# MIPI.net
KiCad netlist of a schematic drawn in Altium Designer
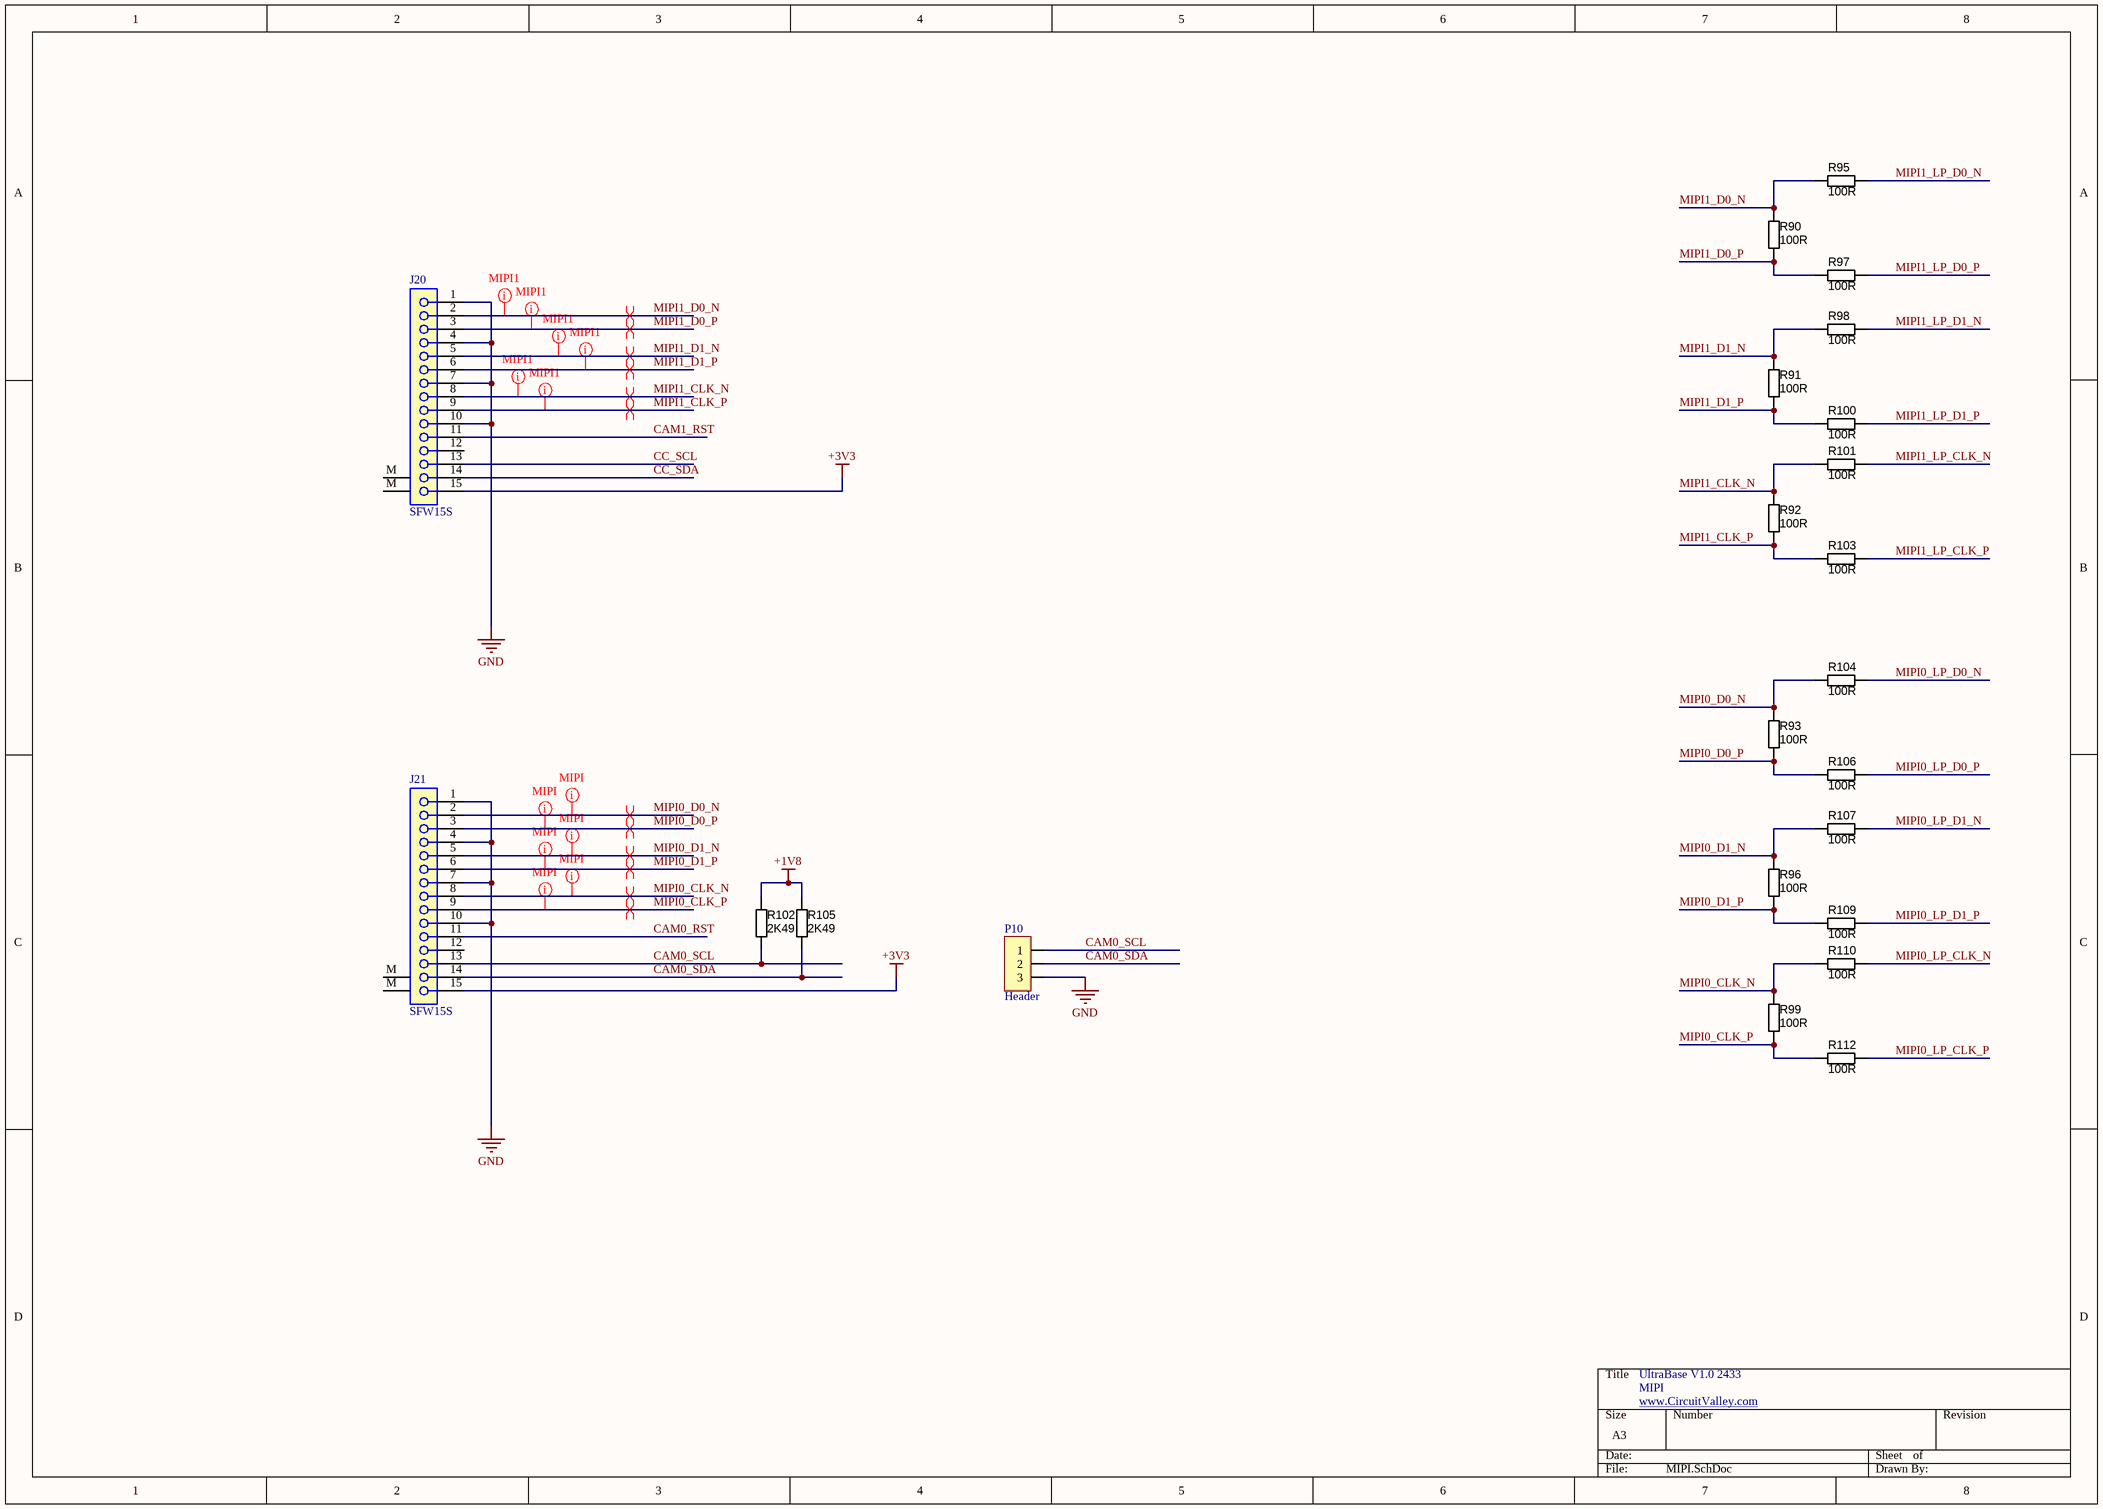
[diagram p0: MIPI.SchDoc]

(export (version "E")
  (design (tool "Eeschema 10.0.6"))
  (components
    (comp (ref "J20")
      (value "SFW15S")
      (footprint "SFW15S-2STMAE1LF")
      (description "15 pin 1mm FPC, RPI Camera")
      (libsource (lib "cvlib") (part "SFW15S"))
    )
    (comp (ref "J21")
      (value "SFW15S")
      (footprint "SFW15S-2STMAE1LF")
      (description "15 pin 1mm FPC, RPI Camera")
      (libsource (lib "cvlib") (part "SFW15S"))
    )
    (comp (ref "P10")
      (value "Header")
      (footprint "Header3x")
      (description "3 Pin Header")
      (libsource (lib "cvlib") (part "Header_3Pin"))
    )
    (comp (ref "R90")
      (value "100R")
      (footprint "RESC1005N")
      (description "Resistor SMD chip 3.3k Ohm 0.063W 5% 0402")
      (fields (field (name "TOLERANCE") "±5%") (field (name "Comment") "Thick Film"))
      (libsource (lib "PBL - Resistors") (part "RES_3K3_0402_5%"))
    )
    (comp (ref "R91")
      (value "100R")
      (footprint "RESC1005N")
      (description "Resistor SMD chip 3.3k Ohm 0.063W 5% 0402")
      (fields (field (name "TOLERANCE") "±5%") (field (name "Comment") "Thick Film"))
      (libsource (lib "PBL - Resistors") (part "RES_3K3_0402_5%"))
    )
    (comp (ref "R92")
      (value "100R")
      (footprint "RESC1005N")
      (description "Resistor SMD chip 3.3k Ohm 0.063W 5% 0402")
      (fields (field (name "TOLERANCE") "±5%") (field (name "Comment") "Thick Film"))
      (libsource (lib "PBL - Resistors") (part "RES_3K3_0402_5%"))
    )
    (comp (ref "R93")
      (value "100R")
      (footprint "RESC1005N")
      (description "Resistor SMD chip 3.3k Ohm 0.063W 5% 0402")
      (fields (field (name "TOLERANCE") "±5%") (field (name "Comment") "Thick Film"))
      (libsource (lib "PBL - Resistors") (part "RES_3K3_0402_5%"))
    )
    (comp (ref "R95")
      (value "100R")
      (footprint "RESC1608N")
      (description "Resistor, SMD chip")
      (fields (field (name "TOLERANCE") "±5%") (field (name "Comment") "RES_NL_0603"))
      (libsource (lib "PBL - Resistors") (part "RES_NL_0603"))
    )
    (comp (ref "R96")
      (value "100R")
      (footprint "RESC1005N")
      (description "Resistor SMD chip 3.3k Ohm 0.063W 5% 0402")
      (fields (field (name "TOLERANCE") "±5%") (field (name "Comment") "Thick Film"))
      (libsource (lib "PBL - Resistors") (part "RES_3K3_0402_5%"))
    )
    (comp (ref "R97")
      (value "100R")
      (footprint "RESC1608N")
      (description "Resistor, SMD chip")
      (fields (field (name "TOLERANCE") "±5%") (field (name "Comment") "RES_NL_0603"))
      (libsource (lib "PBL - Resistors") (part "RES_NL_0603"))
    )
    (comp (ref "R98")
      (value "100R")
      (footprint "RESC1608N")
      (description "Resistor, SMD chip")
      (fields (field (name "TOLERANCE") "±5%") (field (name "Comment") "RES_NL_0603"))
      (libsource (lib "PBL - Resistors") (part "RES_NL_0603"))
    )
    (comp (ref "R99")
      (value "100R")
      (footprint "RESC1005N")
      (description "Resistor SMD chip 3.3k Ohm 0.063W 5% 0402")
      (fields (field (name "TOLERANCE") "±5%") (field (name "Comment") "Thick Film"))
      (libsource (lib "PBL - Resistors") (part "RES_3K3_0402_5%"))
    )
    (comp (ref "R100")
      (value "100R")
      (footprint "RESC1608N")
      (description "Resistor, SMD chip")
      (fields (field (name "TOLERANCE") "±5%") (field (name "Comment") "RES_NL_0603"))
      (libsource (lib "PBL - Resistors") (part "RES_NL_0603"))
    )
    (comp (ref "R101")
      (value "100R")
      (footprint "RESC1608N")
      (description "Resistor, SMD chip")
      (fields (field (name "TOLERANCE") "±5%") (field (name "Comment") "RES_NL_0603"))
      (libsource (lib "PBL - Resistors") (part "RES_NL_0603"))
    )
    (comp (ref "R102")
      (value "2K49")
      (footprint "RESC1608N")
      (description "Resistor, SMD chip")
      (fields (field (name "TOLERANCE") "±5%") (field (name "Comment") "RES_NL_0603"))
      (libsource (lib "") (part "RES_NL_0603_1"))
    )
    (comp (ref "R103")
      (value "100R")
      (footprint "RESC1608N")
      (description "Resistor, SMD chip")
      (fields (field (name "TOLERANCE") "±5%") (field (name "Comment") "RES_NL_0603"))
      (libsource (lib "PBL - Resistors") (part "RES_NL_0603"))
    )
    (comp (ref "R104")
      (value "100R")
      (footprint "RESC1608N")
      (description "Resistor, SMD chip")
      (fields (field (name "TOLERANCE") "±5%") (field (name "Comment") "RES_NL_0603"))
      (libsource (lib "PBL - Resistors") (part "RES_NL_0603"))
    )
    (comp (ref "R105")
      (value "2K49")
      (footprint "RESC1608N")
      (description "Resistor, SMD chip")
      (fields (field (name "TOLERANCE") "±5%") (field (name "Comment") "RES_NL_0603"))
      (libsource (lib "") (part "RES_NL_0603_1"))
    )
    (comp (ref "R106")
      (value "100R")
      (footprint "RESC1608N")
      (description "Resistor, SMD chip")
      (fields (field (name "TOLERANCE") "±5%") (field (name "Comment") "RES_NL_0603"))
      (libsource (lib "PBL - Resistors") (part "RES_NL_0603"))
    )
    (comp (ref "R107")
      (value "100R")
      (footprint "RESC1608N")
      (description "Resistor, SMD chip")
      (fields (field (name "TOLERANCE") "±5%") (field (name "Comment") "RES_NL_0603"))
      (libsource (lib "PBL - Resistors") (part "RES_NL_0603"))
    )
    (comp (ref "R109")
      (value "100R")
      (footprint "RESC1608N")
      (description "Resistor, SMD chip")
      (fields (field (name "TOLERANCE") "±5%") (field (name "Comment") "RES_NL_0603"))
      (libsource (lib "PBL - Resistors") (part "RES_NL_0603"))
    )
    (comp (ref "R110")
      (value "100R")
      (footprint "RESC1608N")
      (description "Resistor, SMD chip")
      (fields (field (name "TOLERANCE") "±5%") (field (name "Comment") "RES_NL_0603"))
      (libsource (lib "PBL - Resistors") (part "RES_NL_0603"))
    )
    (comp (ref "R112")
      (value "100R")
      (footprint "RESC1608N")
      (description "Resistor, SMD chip")
      (fields (field (name "TOLERANCE") "±5%") (field (name "Comment") "RES_NL_0603"))
      (libsource (lib "PBL - Resistors") (part "RES_NL_0603"))
    )
  )
  (nets
    (net (code "1") (name "+1V8") (class "Default")
      (node (ref "R102") (pin "2") (pinfunction "2_2") (pintype "passive"))
      (node (ref "R105") (pin "2") (pinfunction "2_2") (pintype "passive"))
    )
    (net (code "2") (name "+3V3") (class "Default")
      (node (ref "J20") (pin "15") (pinfunction "15_15") (pintype "passive"))
      (node (ref "J21") (pin "15") (pinfunction "15_15") (pintype "passive"))
    )
    (net (code "3") (name "/CAM0_RST") (class "Default")
      (node (ref "J21") (pin "11") (pinfunction "11_11") (pintype "passive"))
    )
    (net (code "4") (name "/CAM0_SCL") (class "Default")
      (node (ref "J21") (pin "13") (pinfunction "13_13") (pintype "passive"))
      (node (ref "P10") (pin "1") (pinfunction "1_1") (pintype "passive"))
      (node (ref "R102") (pin "1") (pinfunction "1_1") (pintype "passive"))
    )
    (net (code "5") (name "/CAM0_SDA") (class "Default")
      (node (ref "J21") (pin "14") (pinfunction "14_14") (pintype "passive"))
      (node (ref "P10") (pin "2") (pinfunction "2_2") (pintype "passive"))
      (node (ref "R105") (pin "1") (pinfunction "1_1") (pintype "passive"))
    )
    (net (code "6") (name "/CAM1_RST") (class "Default")
      (node (ref "J20") (pin "11") (pinfunction "11_11") (pintype "passive"))
    )
    (net (code "7") (name "/CC_SCL") (class "Default")
      (node (ref "J20") (pin "13") (pinfunction "13_13") (pintype "passive"))
    )
    (net (code "8") (name "/CC_SDA") (class "Default")
      (node (ref "J20") (pin "14") (pinfunction "14_14") (pintype "passive"))
    )
    (net (code "9") (name "/MIPI0_CLK_N") (class "Default")
      (node (ref "J21") (pin "8") (pinfunction "8_8") (pintype "passive"))
      (node (ref "R110") (pin "1") (pinfunction "1_1") (pintype "passive"))
      (node (ref "R99") (pin "1") (pinfunction "1_1") (pintype "passive"))
    )
    (net (code "10") (name "/MIPI0_CLK_P") (class "Default")
      (node (ref "J21") (pin "9") (pinfunction "9_9") (pintype "passive"))
      (node (ref "R112") (pin "1") (pinfunction "1_1") (pintype "passive"))
      (node (ref "R99") (pin "2") (pinfunction "2_2") (pintype "passive"))
    )
    (net (code "11") (name "/MIPI0_D0_N") (class "Default")
      (node (ref "J21") (pin "2") (pinfunction "2_2") (pintype "passive"))
      (node (ref "R104") (pin "1") (pinfunction "1_1") (pintype "passive"))
      (node (ref "R93") (pin "1") (pinfunction "1_1") (pintype "passive"))
    )
    (net (code "12") (name "/MIPI0_D0_P") (class "Default")
      (node (ref "J21") (pin "3") (pinfunction "3_3") (pintype "passive"))
      (node (ref "R106") (pin "1") (pinfunction "1_1") (pintype "passive"))
      (node (ref "R93") (pin "2") (pinfunction "2_2") (pintype "passive"))
    )
    (net (code "13") (name "/MIPI0_D1_N") (class "Default")
      (node (ref "J21") (pin "5") (pinfunction "5_5") (pintype "passive"))
      (node (ref "R107") (pin "1") (pinfunction "1_1") (pintype "passive"))
      (node (ref "R96") (pin "1") (pinfunction "1_1") (pintype "passive"))
    )
    (net (code "14") (name "/MIPI0_D1_P") (class "Default")
      (node (ref "J21") (pin "6") (pinfunction "6_6") (pintype "passive"))
      (node (ref "R109") (pin "1") (pinfunction "1_1") (pintype "passive"))
      (node (ref "R96") (pin "2") (pinfunction "2_2") (pintype "passive"))
    )
    (net (code "15") (name "/MIPI0_LP_CLK_N") (class "Default")
      (node (ref "R110") (pin "2") (pinfunction "2_2") (pintype "passive"))
    )
    (net (code "16") (name "/MIPI0_LP_CLK_P") (class "Default")
      (node (ref "R112") (pin "2") (pinfunction "2_2") (pintype "passive"))
    )
    (net (code "17") (name "/MIPI0_LP_D0_N") (class "Default")
      (node (ref "R104") (pin "2") (pinfunction "2_2") (pintype "passive"))
    )
    (net (code "18") (name "/MIPI0_LP_D0_P") (class "Default")
      (node (ref "R106") (pin "2") (pinfunction "2_2") (pintype "passive"))
    )
    (net (code "19") (name "/MIPI0_LP_D1_N") (class "Default")
      (node (ref "R107") (pin "2") (pinfunction "2_2") (pintype "passive"))
    )
    (net (code "20") (name "/MIPI0_LP_D1_P") (class "Default")
      (node (ref "R109") (pin "2") (pinfunction "2_2") (pintype "passive"))
    )
    (net (code "21") (name "/MIPI1_CLK_N") (class "Default")
      (node (ref "J20") (pin "8") (pinfunction "8_8") (pintype "passive"))
      (node (ref "R101") (pin "1") (pinfunction "1_1") (pintype "passive"))
      (node (ref "R92") (pin "1") (pinfunction "1_1") (pintype "passive"))
    )
    (net (code "22") (name "/MIPI1_CLK_P") (class "Default")
      (node (ref "J20") (pin "9") (pinfunction "9_9") (pintype "passive"))
      (node (ref "R103") (pin "1") (pinfunction "1_1") (pintype "passive"))
      (node (ref "R92") (pin "2") (pinfunction "2_2") (pintype "passive"))
    )
    (net (code "23") (name "/MIPI1_D0_N") (class "Default")
      (node (ref "J20") (pin "2") (pinfunction "2_2") (pintype "passive"))
      (node (ref "R90") (pin "1") (pinfunction "1_1") (pintype "passive"))
      (node (ref "R95") (pin "1") (pinfunction "1_1") (pintype "passive"))
    )
    (net (code "24") (name "/MIPI1_D0_P") (class "Default")
      (node (ref "J20") (pin "3") (pinfunction "3_3") (pintype "passive"))
      (node (ref "R90") (pin "2") (pinfunction "2_2") (pintype "passive"))
      (node (ref "R97") (pin "1") (pinfunction "1_1") (pintype "passive"))
    )
    (net (code "25") (name "/MIPI1_D1_N") (class "Default")
      (node (ref "J20") (pin "5") (pinfunction "5_5") (pintype "passive"))
      (node (ref "R91") (pin "1") (pinfunction "1_1") (pintype "passive"))
      (node (ref "R98") (pin "1") (pinfunction "1_1") (pintype "passive"))
    )
    (net (code "26") (name "/MIPI1_D1_P") (class "Default")
      (node (ref "J20") (pin "6") (pinfunction "6_6") (pintype "passive"))
      (node (ref "R100") (pin "1") (pinfunction "1_1") (pintype "passive"))
      (node (ref "R91") (pin "2") (pinfunction "2_2") (pintype "passive"))
    )
    (net (code "27") (name "/MIPI1_LP_CLK_N") (class "Default")
      (node (ref "R101") (pin "2") (pinfunction "2_2") (pintype "passive"))
    )
    (net (code "28") (name "/MIPI1_LP_CLK_P") (class "Default")
      (node (ref "R103") (pin "2") (pinfunction "2_2") (pintype "passive"))
    )
    (net (code "29") (name "/MIPI1_LP_D0_N") (class "Default")
      (node (ref "R95") (pin "2") (pinfunction "2_2") (pintype "passive"))
    )
    (net (code "30") (name "/MIPI1_LP_D0_P") (class "Default")
      (node (ref "R97") (pin "2") (pinfunction "2_2") (pintype "passive"))
    )
    (net (code "31") (name "/MIPI1_LP_D1_N") (class "Default")
      (node (ref "R98") (pin "2") (pinfunction "2_2") (pintype "passive"))
    )
    (net (code "32") (name "/MIPI1_LP_D1_P") (class "Default")
      (node (ref "R100") (pin "2") (pinfunction "2_2") (pintype "passive"))
    )
    (net (code "33") (name "GND") (class "Default")
      (node (ref "J20") (pin "1") (pinfunction "1_1") (pintype "passive"))
      (node (ref "J20") (pin "10") (pinfunction "10_10") (pintype "passive"))
      (node (ref "J20") (pin "4") (pinfunction "4_4") (pintype "passive"))
      (node (ref "J20") (pin "7") (pinfunction "7_7") (pintype "passive"))
      (node (ref "J21") (pin "1") (pinfunction "1_1") (pintype "passive"))
      (node (ref "J21") (pin "10") (pinfunction "10_10") (pintype "passive"))
      (node (ref "J21") (pin "4") (pinfunction "4_4") (pintype "passive"))
      (node (ref "J21") (pin "7") (pinfunction "7_7") (pintype "passive"))
      (node (ref "P10") (pin "3") (pinfunction "3_3") (pintype "passive"))
    )
    (net (code "34") (name "unconnected-(J20-16-PadM)") (class "Default")
      (node (ref "J20") (pin "M") (pinfunction "16_M") (pintype "passive"))
    )
    (net (code "35") (name "unconnected-(J20-17-PadM)") (class "Default")
      (node (ref "J20") (pin "M") (pinfunction "17_M") (pintype "passive"))
    )
    (net (code "36") (name "unconnected-(J20-Pad12)") (class "Default")
      (node (ref "J20") (pin "12") (pinfunction "12_12") (pintype "passive"))
    )
    (net (code "37") (name "unconnected-(J21-16-PadM)") (class "Default")
      (node (ref "J21") (pin "M") (pinfunction "16_M") (pintype "passive"))
    )
    (net (code "38") (name "unconnected-(J21-17-PadM)") (class "Default")
      (node (ref "J21") (pin "M") (pinfunction "17_M") (pintype "passive"))
    )
    (net (code "39") (name "unconnected-(J21-Pad12)") (class "Default")
      (node (ref "J21") (pin "12") (pinfunction "12_12") (pintype "passive"))
    )
  )
)
